# Main.net
KiCad netlist of a schematic drawn in Altium Designer
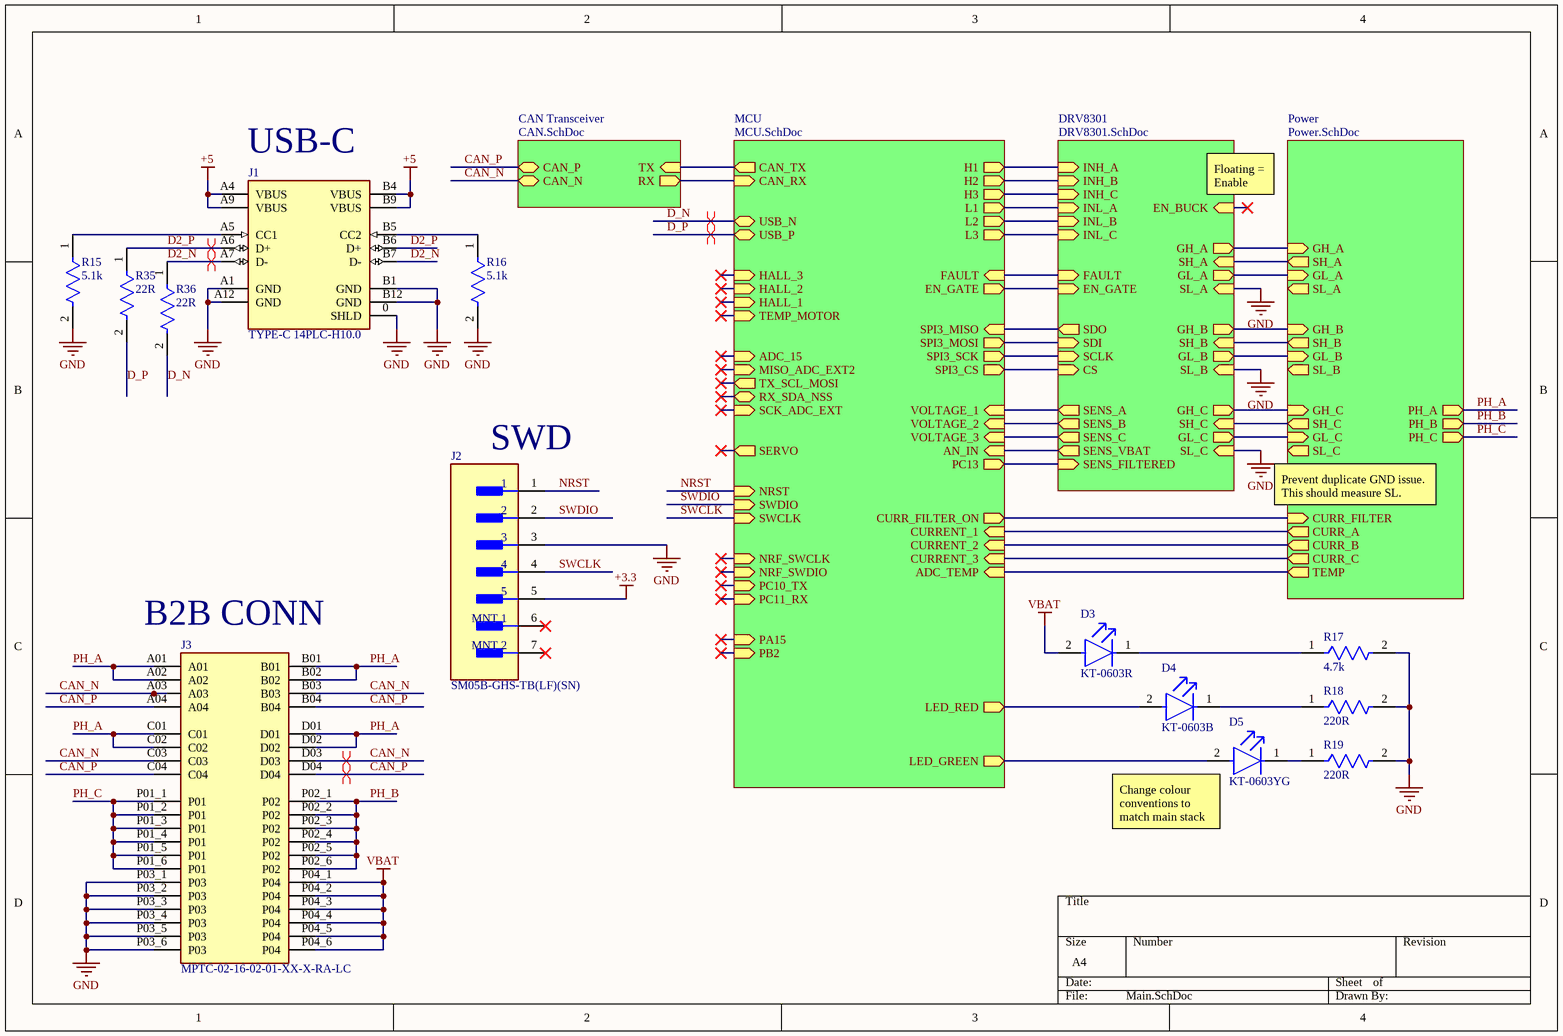
[diagram p0: Main.SchDoc]

(export (version "E")
  (design (tool "Eeschema 10.0.6"))
  (components
    (comp (ref "D3")
      (value "KT-0603R")
      (footprint "KT-0603R")
      (libsource (lib "BEESC_Lib") (part "KT-0603R"))
    )
    (comp (ref "D4")
      (value "KT-0603B")
      (footprint "KT-0603B")
      (description "100mW 120° 175mcd 3.1V 460nm~475nm 469nm 5mA Blue Water Clear 0603 LED Indication - Discrete ROHS")
      (libsource (lib "BEESC_Lib") (part "KT-0603B"))
    )
    (comp (ref "D5")
      (value "KT-0603YG")
      (footprint "KT-0603YG")
      (libsource (lib "BEESC_Lib") (part "KT-0603YG"))
    )
    (comp (ref "J1")
      (value "TYPE-C 14PLC-H10.0")
      (footprint "TYPE-C 14PLC-H10.0")
      (libsource (lib "BEESC_Lib") (part "TYPE-C 14PLC-H10.0"))
    )
    (comp (ref "J2")
      (value "SM05B-GHS-TB(LF)(SN)")
      (footprint "SM05B-GHS-TB(LF)(SN)")
      (description "Connector Header, GH Series, 5 Position, 1.25mm, Surface Mount, Right Angle, Tin, Natural")
      (libsource (lib "BEESC_Lib") (part "SM05B-GHS-TB(LF)(SN)"))
    )
    (comp (ref "J3")
      (value "MPTC-02-16-02-01-XX-X-RA-LC")
      (footprint "SAMTEC_MPTC-02-16-02-01-XX-X-RA-LC")
      (fields (field (name "MF") "Samtec"))
      (libsource (lib "BumbleBee Autonomous Systems - NUS") (part "MPTC-02-16-02-01-XX-X-RA-LC"))
    )
    (comp (ref "R15")
      (value "5.1k")
      (footprint "FP-AC0402-MFG")
      (libsource (lib "BEESC_Lib") (part "0402WGF5101TCE"))
    )
    (comp (ref "R16")
      (value "5.1k")
      (footprint "FP-AC0402-MFG")
      (libsource (lib "BEESC_Lib") (part "0402WGF5101TCE"))
    )
    (comp (ref "R17")
      (value "4.7k")
      (footprint "FP-AC0402-MFG")
      (libsource (lib "BEESC_Lib") (part "0402WGF4701TCE"))
    )
    (comp (ref "R18")
      (value "220R")
      (footprint "FP-AC0402-MFG")
      (libsource (lib "BEESC_Lib") (part "0402WGF2200TCE"))
    )
    (comp (ref "R19")
      (value "220R")
      (footprint "FP-AC0402-MFG")
      (libsource (lib "BEESC_Lib") (part "0402WGF2200TCE"))
    )
    (comp (ref "R35")
      (value "22R")
      (footprint "FP-AC0402-MFG")
      (libsource (lib "BEESC_Lib") (part "0402WGF220JTCE"))
    )
    (comp (ref "R36")
      (value "22R")
      (footprint "FP-AC0402-MFG")
      (libsource (lib "BEESC_Lib") (part "0402WGF220JTCE"))
    )
  )
  (nets
    (net (code "1") (name "+3.3") (class "Default")
      (node (ref "J2") (pin "5") (pinfunction "5_5") (pintype "passive"))
    )
    (net (code "2") (name "+5") (class "Default")
      (node (ref "J1") (pin "A4") (pinfunction "VBUS_A4") (pintype "power_in"))
      (node (ref "J1") (pin "A9") (pinfunction "VBUS_A9") (pintype "power_in"))
      (node (ref "J1") (pin "B4") (pinfunction "VBUS_B4") (pintype "power_in"))
      (node (ref "J1") (pin "B9") (pinfunction "VBUS_B9") (pintype "power_in"))
    )
    (net (code "4") (name "/CAN_N") (class "Default")
      (node (ref "J3") (pin "A03") (pinfunction "A03_A03") (pintype "passive"))
      (node (ref "J3") (pin "B03") (pinfunction "B03_B03") (pintype "passive"))
      (node (ref "J3") (pin "C03") (pinfunction "C03_C03") (pintype "passive"))
      (node (ref "J3") (pin "D03") (pinfunction "D03_D03") (pintype "passive"))
    )
    (net (code "5") (name "/CAN_P") (class "Default")
      (node (ref "J3") (pin "A04") (pinfunction "A04_A04") (pintype "passive"))
      (node (ref "J3") (pin "B04") (pinfunction "B04_B04") (pintype "passive"))
      (node (ref "J3") (pin "C04") (pinfunction "C04_C04") (pintype "passive"))
      (node (ref "J3") (pin "D04") (pinfunction "D04_D04") (pintype "passive"))
    )
    (net (code "11") (name "/D2_N") (class "Default")
      (node (ref "J1") (pin "A7") (pinfunction "D-_A7") (pintype "bidirectional"))
      (node (ref "J1") (pin "B7") (pinfunction "D-_B7") (pintype "bidirectional"))
      (node (ref "R36") (pin "1") (pinfunction "1_1") (pintype "passive"))
    )
    (net (code "12") (name "/D2_P") (class "Default")
      (node (ref "J1") (pin "A6") (pinfunction "D+_A6") (pintype "bidirectional"))
      (node (ref "J1") (pin "B6") (pinfunction "D+_B6") (pintype "bidirectional"))
      (node (ref "R35") (pin "1") (pinfunction "1_1") (pintype "passive"))
    )
    (net (code "13") (name "/D_N") (class "Default")
      (node (ref "R36") (pin "2") (pinfunction "2_2") (pintype "passive"))
    )
    (net (code "14") (name "/D_P") (class "Default")
      (node (ref "R35") (pin "2") (pinfunction "2_2") (pintype "passive"))
    )
    (net (code "33") (name "/LED_GREEN") (class "Default")
      (node (ref "D5") (pin "2") (pinfunction "A_2") (pintype "passive"))
    )
    (net (code "34") (name "/LED_RED") (class "Default")
      (node (ref "D4") (pin "2") (pinfunction "A_2") (pintype "passive"))
    )
    (net (code "38") (name "/NRST") (class "Default")
      (node (ref "J2") (pin "1") (pinfunction "1_1") (pintype "passive"))
    )
    (net (code "44") (name "/PH_A") (class "Default")
      (node (ref "J3") (pin "A01") (pinfunction "A01_A01") (pintype "passive"))
      (node (ref "J3") (pin "A02") (pinfunction "A02_A02") (pintype "passive"))
      (node (ref "J3") (pin "B01") (pinfunction "B01_B01") (pintype "passive"))
      (node (ref "J3") (pin "B02") (pinfunction "B02_B02") (pintype "passive"))
      (node (ref "J3") (pin "C01") (pinfunction "C01_C01") (pintype "passive"))
      (node (ref "J3") (pin "C02") (pinfunction "C02_C02") (pintype "passive"))
      (node (ref "J3") (pin "D01") (pinfunction "D01_D01") (pintype "passive"))
      (node (ref "J3") (pin "D02") (pinfunction "D02_D02") (pintype "passive"))
    )
    (net (code "45") (name "/PH_B") (class "Default")
      (node (ref "J3") (pin "P02_1") (pinfunction "P02_P02_1") (pintype "power_in"))
      (node (ref "J3") (pin "P02_2") (pinfunction "P02_P02_2") (pintype "power_in"))
      (node (ref "J3") (pin "P02_3") (pinfunction "P02_P02_3") (pintype "power_in"))
      (node (ref "J3") (pin "P02_4") (pinfunction "P02_P02_4") (pintype "power_in"))
      (node (ref "J3") (pin "P02_5") (pinfunction "P02_P02_5") (pintype "power_in"))
      (node (ref "J3") (pin "P02_6") (pinfunction "P02_P02_6") (pintype "power_in"))
    )
    (net (code "46") (name "/PH_C") (class "Default")
      (node (ref "J3") (pin "P01_1") (pinfunction "P01_P01_1") (pintype "power_in"))
      (node (ref "J3") (pin "P01_2") (pinfunction "P01_P01_2") (pintype "power_in"))
      (node (ref "J3") (pin "P01_3") (pinfunction "P01_P01_3") (pintype "power_in"))
      (node (ref "J3") (pin "P01_4") (pinfunction "P01_P01_4") (pintype "power_in"))
      (node (ref "J3") (pin "P01_5") (pinfunction "P01_P01_5") (pintype "power_in"))
      (node (ref "J3") (pin "P01_6") (pinfunction "P01_P01_6") (pintype "power_in"))
    )
    (net (code "65") (name "/SWCLK") (class "Default")
      (node (ref "J2") (pin "4") (pinfunction "4_4") (pintype "passive"))
    )
    (net (code "66") (name "/SWDIO") (class "Default")
      (node (ref "J2") (pin "2") (pinfunction "2_2") (pintype "passive"))
    )
    (net (code "70") (name "GND") (class "Default")
      (node (ref "J1") (pin "0") (pinfunction "SHLD_0") (pintype "power_in"))
      (node (ref "J1") (pin "A1") (pinfunction "GND_A1") (pintype "power_in"))
      (node (ref "J1") (pin "A12") (pinfunction "GND_A12") (pintype "power_in"))
      (node (ref "J1") (pin "B1") (pinfunction "GND_B1") (pintype "power_in"))
      (node (ref "J1") (pin "B12") (pinfunction "GND_B12") (pintype "power_in"))
      (node (ref "J2") (pin "3") (pinfunction "3_3") (pintype "passive"))
      (node (ref "J3") (pin "P03_1") (pinfunction "P03_P03_1") (pintype "power_in"))
      (node (ref "J3") (pin "P03_2") (pinfunction "P03_P03_2") (pintype "power_in"))
      (node (ref "J3") (pin "P03_3") (pinfunction "P03_P03_3") (pintype "power_in"))
      (node (ref "J3") (pin "P03_4") (pinfunction "P03_P03_4") (pintype "power_in"))
      (node (ref "J3") (pin "P03_5") (pinfunction "P03_P03_5") (pintype "power_in"))
      (node (ref "J3") (pin "P03_6") (pinfunction "P03_P03_6") (pintype "power_in"))
      (node (ref "R15") (pin "2") (pinfunction "2_2") (pintype "passive"))
      (node (ref "R16") (pin "2") (pinfunction "2_2") (pintype "passive"))
      (node (ref "R17") (pin "2") (pinfunction "2_2") (pintype "passive"))
      (node (ref "R18") (pin "2") (pinfunction "2_2") (pintype "passive"))
      (node (ref "R19") (pin "2") (pinfunction "2_2") (pintype "passive"))
    )
    (net (code "71") (name "Net-(D3-C)") (class "Default")
      (node (ref "D3") (pin "1") (pinfunction "C_1") (pintype "passive"))
      (node (ref "R17") (pin "1") (pinfunction "1_1") (pintype "passive"))
    )
    (net (code "72") (name "Net-(D4-C)") (class "Default")
      (node (ref "D4") (pin "1") (pinfunction "C_1") (pintype "passive"))
      (node (ref "R18") (pin "1") (pinfunction "1_1") (pintype "passive"))
    )
    (net (code "73") (name "Net-(D5-C)") (class "Default")
      (node (ref "D5") (pin "1") (pinfunction "C_1") (pintype "passive"))
      (node (ref "R19") (pin "1") (pinfunction "1_1") (pintype "passive"))
    )
    (net (code "74") (name "Net-(J1-CC1)") (class "Default")
      (node (ref "J1") (pin "A5") (pinfunction "CC1_A5") (pintype "input"))
      (node (ref "R15") (pin "1") (pinfunction "1_1") (pintype "passive"))
    )
    (net (code "75") (name "Net-(J1-CC2)") (class "Default")
      (node (ref "J1") (pin "B5") (pinfunction "CC2_B5") (pintype "input"))
      (node (ref "R16") (pin "1") (pinfunction "1_1") (pintype "passive"))
    )
    (net (code "76") (name "VBAT") (class "Default")
      (node (ref "D3") (pin "2") (pinfunction "A_2") (pintype "passive"))
      (node (ref "J3") (pin "P04_1") (pinfunction "P04_P04_1") (pintype "power_in"))
      (node (ref "J3") (pin "P04_2") (pinfunction "P04_P04_2") (pintype "power_in"))
      (node (ref "J3") (pin "P04_3") (pinfunction "P04_P04_3") (pintype "power_in"))
      (node (ref "J3") (pin "P04_4") (pinfunction "P04_P04_4") (pintype "power_in"))
      (node (ref "J3") (pin "P04_5") (pinfunction "P04_P04_5") (pintype "power_in"))
      (node (ref "J3") (pin "P04_6") (pinfunction "P04_P04_6") (pintype "power_in"))
    )
    (net (code "77") (name "unconnected-(J2-MNT_1-Pad6)") (class "Default")
      (node (ref "J2") (pin "6") (pinfunction "MNT_1_6") (pintype "passive+no_connect"))
    )
    (net (code "78") (name "unconnected-(J2-MNT_2-Pad7)") (class "Default")
      (node (ref "J2") (pin "7") (pinfunction "MNT_2_7") (pintype "passive+no_connect"))
    )
  )
)
